# Power.net
KiCad netlist of a schematic drawn in Altium Designer
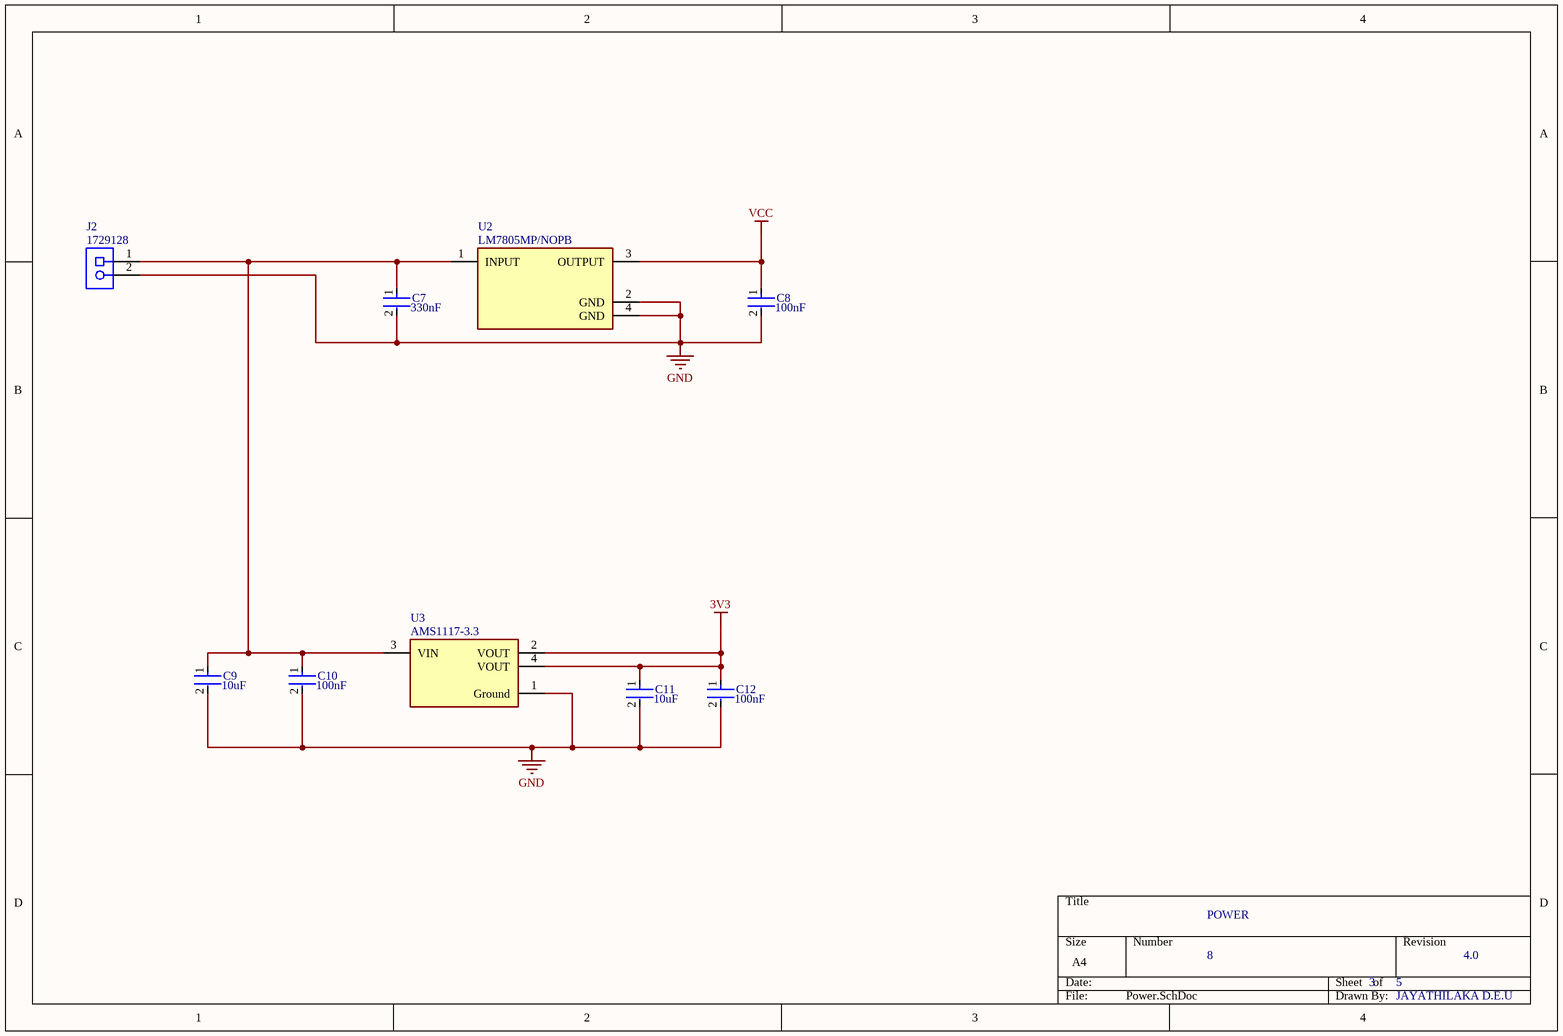
[diagram p0: Power.SchDoc]

(export (version "E")
  (design (tool "Eeschema 10.0.6"))
  (components
    (comp (ref "C7")
      (value "330nF")
      (footprint "FP-CC1206-0_3-1_8-MFG")
      (description "CAP CER X7R 1206")
      (fields (field (name "Comment") "CC1206KKX7R0BB334"))
      (libsource (lib "Altium Content Vault") (part "b4654b650e69147ec39a6b967a45e02"))
    )
    (comp (ref "C8")
      (value "GRM31C5C1H104JA01L")
      (footprint "FP-GRM31C-0_2-e0_3_0_8-IPC_B")
      (description "Chip Multilayer Ceramic Capacitors for General Purpose, 1206, 0.10uF, C0G, 30ppm/°C, 5%, 50V")
      (fields
        (field (name "VOLTAGE") "50V")
        (field (name "CAPACITANCE") "100nF")
        (field (name "TOLERANCE") "5%")
      )
      (libsource (lib "Altium Content Vault") (part "02cd4be3c70576c341d710602a673aa"))
    )
    (comp (ref "C9")
      (value "10uF")
      (footprint "FP-CL31B106KBHNNNE-MFG")
      (description "CAP CER 10UF 50V X7R 1206")
      (fields (field (name "MANUFACTURER") "Samsung") (field (name "TOLERANCE") "10%"))
      (libsource (lib "Altium Content Vault") (part "b4654b650e69147ec39a6b967a45e02"))
    )
    (comp (ref "C10")
      (value "GRM31C5C1H104JA01L")
      (footprint "FP-GRM31C-0_2-e0_3_0_8-IPC_B")
      (description "Chip Multilayer Ceramic Capacitors for General Purpose, 1206, 0.10uF, C0G, 30ppm/°C, 5%, 50V")
      (fields
        (field (name "VOLTAGE") "50V")
        (field (name "CAPACITANCE") "100nF")
        (field (name "TOLERANCE") "5%")
      )
      (libsource (lib "Altium Content Vault") (part "02cd4be3c70576c341d710602a673aa"))
    )
    (comp (ref "C11")
      (value "10uF")
      (footprint "FP-CL31B106KBHNNNE-MFG")
      (description "CAP CER 10UF 50V X7R 1206")
      (fields (field (name "MANUFACTURER") "Samsung") (field (name "TOLERANCE") "10%"))
      (libsource (lib "Altium Content Vault") (part "b4654b650e69147ec39a6b967a45e02"))
    )
    (comp (ref "C12")
      (value "GRM31C5C1H104JA01L")
      (footprint "FP-GRM31C-0_2-e0_3_0_8-IPC_B")
      (description "Chip Multilayer Ceramic Capacitors for General Purpose, 1206, 0.10uF, C0G, 30ppm/°C, 5%, 50V")
      (fields
        (field (name "VOLTAGE") "50V")
        (field (name "CAPACITANCE") "100nF")
        (field (name "TOLERANCE") "5%")
      )
      (libsource (lib "Altium Content Vault") (part "02cd4be3c70576c341d710602a673aa"))
    )
    (comp (ref "J2")
      (value "1729128")
      (footprint "PHOE-1729128-2_V")
      (description "PCB Terminal Block, 13.5 A, 400 V, 2-Pin THD, RoHS, Bulk")
      (fields (field (name "MANUFACTURER") "Phoenix Contact"))
      (libsource (lib "Altium Content Vault") (part "CN-2P-F-R2"))
    )
    (comp (ref "U2")
      (value "LM7805MP/NOPB")
      (footprint "FP-DCY0004A-MFG")
      (description "IC REG LINEAR 5V 1.5A SOT223-4")
      (fields
        (field (name "OCTOPART") "https://octopart.com/lm7805mp%2Fnopb-texas+instruments-74629991")
        (field (name "MANUFACTURER") "Texas Instruments")
      )
      (libsource (lib "Altium Content Vault") (part "84c6965c160f0d7e9bd6a72b5b454c6"))
    )
    (comp (ref "U3")
      (value "AMS1117-3.3")
      (footprint "FP-AMS1117-IPC_C")
      (description "LDO Voltage Regulators 1A, 3.3V")
      (fields
        (field (name "OCTOPART") "https://octopart.com/ams1117-3.3-advanced+monolithic+systems-25899300")
        (field (name "MANUFACTURER") "Advanced Monolithic Systems")
      )
      (libsource (lib "Altium Content Vault") (part "8bdbb5f8e77002000e30dd2845d0354"))
    )
  )
  (nets
    (net (code "1") (name "3V3") (class "Default")
      (node (ref "C11") (pin "1") (pinfunction "1_1") (pintype "passive"))
      (node (ref "C12") (pin "1") (pinfunction "1_1") (pintype "passive"))
      (node (ref "U3") (pin "2") (pinfunction "VOUT_2") (pintype "passive"))
      (node (ref "U3") (pin "4") (pinfunction "VOUT_4") (pintype "passive"))
    )
    (net (code "2") (name "GND") (class "Default")
      (node (ref "C10") (pin "2") (pinfunction "2_2") (pintype "passive"))
      (node (ref "C11") (pin "2") (pinfunction "2_2") (pintype "passive"))
      (node (ref "C12") (pin "2") (pinfunction "2_2") (pintype "passive"))
      (node (ref "C7") (pin "2") (pinfunction "2_2") (pintype "passive"))
      (node (ref "C8") (pin "2") (pinfunction "2_2") (pintype "passive"))
      (node (ref "C9") (pin "2") (pinfunction "2_2") (pintype "passive"))
      (node (ref "J2") (pin "2") (pinfunction "2_2") (pintype "passive"))
      (node (ref "U2") (pin "2") (pinfunction "GND_2") (pintype "power_in"))
      (node (ref "U2") (pin "4") (pinfunction "GND_4") (pintype "power_in"))
      (node (ref "U3") (pin "1") (pinfunction "Ground_1") (pintype "power_in"))
    )
    (net (code "3") (name "Net-(U2-INPUT)") (class "Default")
      (node (ref "C10") (pin "1") (pinfunction "1_1") (pintype "passive"))
      (node (ref "C7") (pin "1") (pinfunction "1_1") (pintype "passive"))
      (node (ref "C9") (pin "1") (pinfunction "1_1") (pintype "passive"))
      (node (ref "J2") (pin "1") (pinfunction "1_1") (pintype "passive"))
      (node (ref "U2") (pin "1") (pinfunction "INPUT_1") (pintype "power_in"))
      (node (ref "U3") (pin "3") (pinfunction "VIN_3") (pintype "power_in"))
    )
    (net (code "4") (name "VCC") (class "Default")
      (node (ref "C8") (pin "1") (pinfunction "1_1") (pintype "passive"))
      (node (ref "U2") (pin "3") (pinfunction "OUTPUT_3") (pintype "power_in"))
    )
  )
)
